# RightPannel.net
KiCad netlist of a schematic drawn in Altium Designer
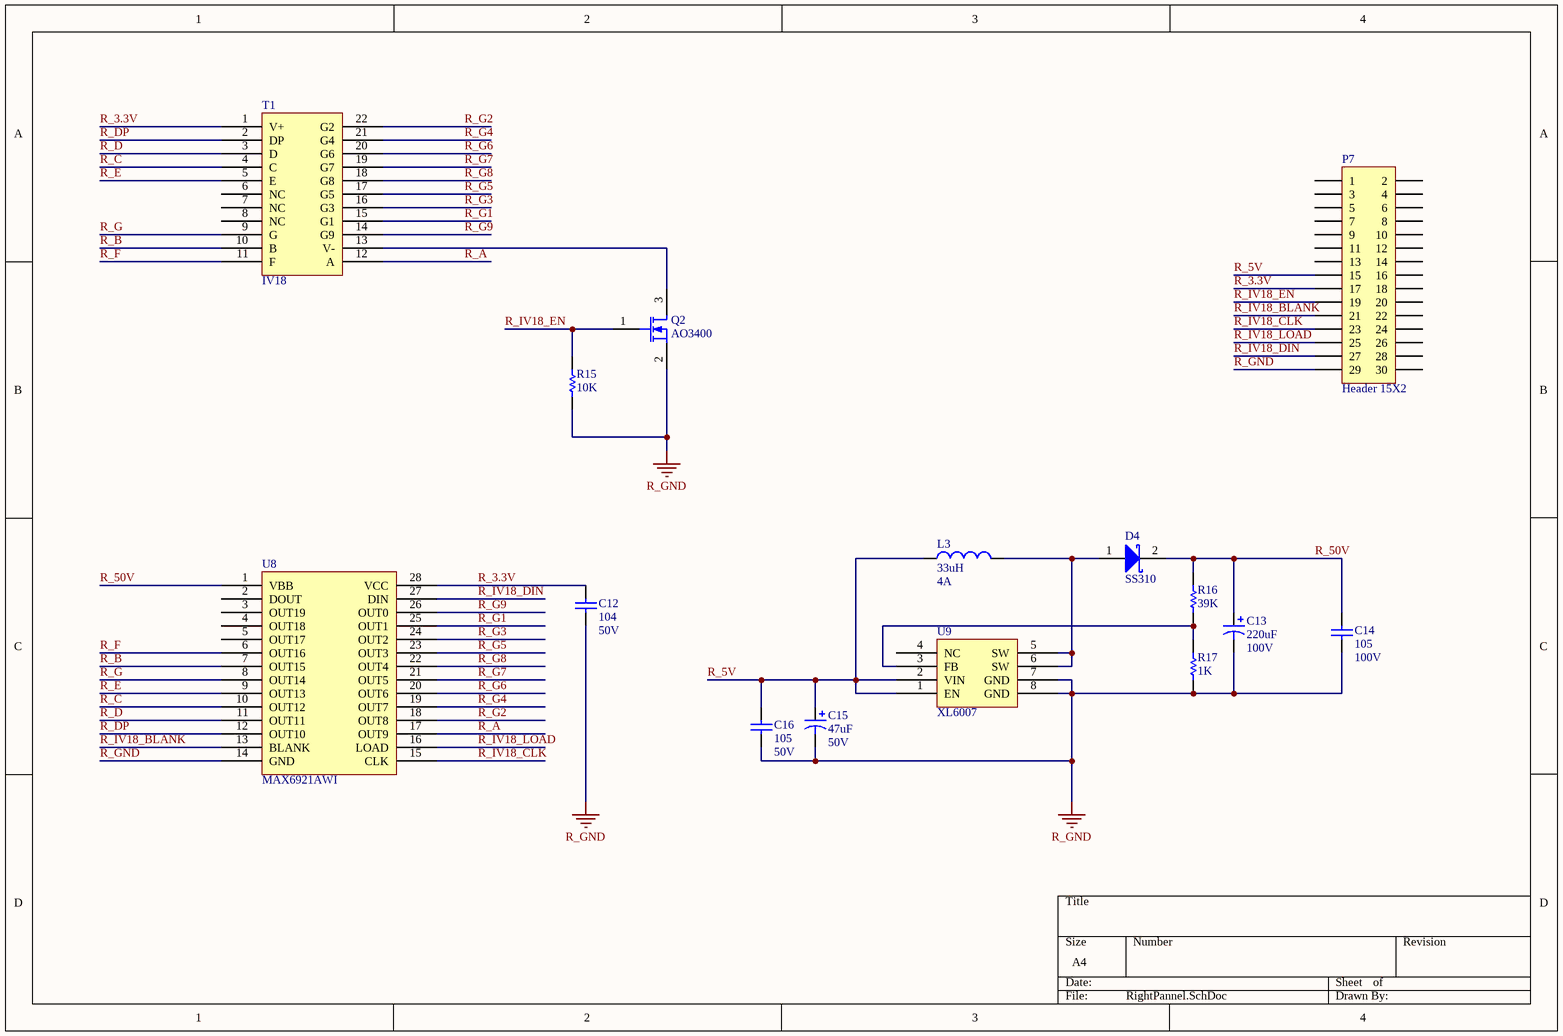
[diagram p0: RightPannel.SchDoc]

(export (version "E")
  (design (tool "Eeschema 10.0.6"))
  (components
    (comp (ref "C12")
      (value "50V")
      (footprint "NeoIVClock:CAPC1608L")
      (description "Capacitor")
      (fields (field (name "ALTIUM_VALUE") "104") (field (name "PUBLISHER") "Altium Limited"))
      (libsource (lib "Miscellaneous Devices") (part "Cap"))
    )
    (comp (ref "C13")
      (value "100V")
      (footprint "NeoIVClock:SMD-EC-F16")
      (description "Polarized Capacitor (Radial)")
      (fields (field (name "ALTIUM_VALUE") "220uF") (field (name "PUBLISHER") "Altium Limited"))
      (libsource (lib "Miscellaneous Devices") (part "Cap Pol1"))
    )
    (comp (ref "C14")
      (value "100V")
      (footprint "NeoIVClock:CAPC2012L")
      (description "Capacitor")
      (fields (field (name "ALTIUM_VALUE") "105") (field (name "PUBLISHER") "Altium Limited"))
      (libsource (lib "Miscellaneous Devices") (part "Cap"))
    )
    (comp (ref "C15")
      (value "50V")
      (footprint "NeoIVClock:SMD-EC-F6.3")
      (description "Polarized Capacitor (Radial)")
      (fields (field (name "ALTIUM_VALUE") "47uF") (field (name "PUBLISHER") "Altium Limited"))
      (libsource (lib "Miscellaneous Devices") (part "Cap Pol1"))
    )
    (comp (ref "C16")
      (value "50V")
      (footprint "NeoIVClock:CAPC1608L")
      (description "Capacitor")
      (fields (field (name "ALTIUM_VALUE") "105") (field (name "PUBLISHER") "Altium Limited"))
      (libsource (lib "Miscellaneous Devices") (part "Cap"))
    )
    (comp (ref "D4")
      (value "SS310")
      (footprint "NeoIVClock:DO-214AC-SMA")
      (description "Schottky Diode")
      (fields (field (name "PUBLISHER") "Altium Limited"))
      (libsource (lib "Miscellaneous Devices") (part "D Schottky"))
    )
    (comp (ref "L3")
      (value "4A")
      (footprint "NeoIVClock:CYH125")
      (description "Inductor")
      (fields (field (name "ALTIUM_VALUE") "33uH") (field (name "PUBLISHER") "Altium Limited"))
      (libsource (lib "Miscellaneous Devices") (part "Inductor"))
    )
    (comp (ref "P7")
      (value "Header 15X2")
      (footprint "HDR2X15")
      (description "Header, 15-Pin, Dual row")
      (fields (field (name "PUBLISHER") "Altium Limited"))
      (libsource (lib "Miscellaneous Connectors") (part "Header 15X2"))
    )
    (comp (ref "Q2")
      (value "AO3400")
      (footprint "NeoIVClock:SOT-23B_L")
      (description "N-Channel MOSFET")
      (fields (field (name "PUBLISHER") "Altium Limited"))
      (libsource (lib "Miscellaneous Devices") (part "MOSFET-N"))
    )
    (comp (ref "R15")
      (value "10K")
      (footprint "NeoIVClock:RESC1608L")
      (description "Resistor")
      (fields (field (name "Comment") "Res1") (field (name "PUBLISHER") "Altium Limited"))
      (libsource (lib "Miscellaneous Devices") (part "Res1"))
    )
    (comp (ref "R16")
      (value "39K")
      (footprint "NeoIVClock:RESC1608L")
      (description "Resistor")
      (fields (field (name "Comment") "Res1") (field (name "PUBLISHER") "Altium Limited"))
      (libsource (lib "Miscellaneous Devices") (part "Res1"))
    )
    (comp (ref "R17")
      (value "1K")
      (footprint "NeoIVClock:RESC1608L")
      (description "Resistor")
      (fields (field (name "Comment") "Res1") (field (name "PUBLISHER") "Altium Limited"))
      (libsource (lib "Miscellaneous Devices") (part "Res1"))
    )
    (comp (ref "T1")
      (value "IV18")
      (footprint "NeoIVClock:IV18")
      (libsource (lib "NeoIVClock") (part "IV18"))
    )
    (comp (ref "U8")
      (value "MAX6921AWI")
      (footprint "NeoIVClock:SOIC127P1032X265-28N")
      (libsource (lib "NeoIVClock") (part "MAX6921AWI"))
    )
    (comp (ref "U9")
      (value "XL6007")
      (footprint "NeoIVClock:SOP127P780-8L")
      (libsource (lib "NeoIVClock") (part "XL6007"))
    )
  )
  (nets
    (net (code "1") (name "/R_3.3V") (class "Default")
      (node (ref "C12") (pin "2") (pinfunction "2_2") (pintype "passive"))
      (node (ref "P7") (pin "17") (pinfunction "17_17") (pintype "passive"))
      (node (ref "T1") (pin "1") (pinfunction "V+_1") (pintype "passive"))
      (node (ref "U8") (pin "28") (pinfunction "VCC_28") (pintype "passive"))
    )
    (net (code "2") (name "/R_5V") (class "Default")
      (node (ref "C15") (pin "1") (pinfunction "1_1") (pintype "passive"))
      (node (ref "C16") (pin "2") (pinfunction "2_2") (pintype "passive"))
      (node (ref "L3") (pin "1") (pinfunction "1_1") (pintype "passive"))
      (node (ref "P7") (pin "15") (pinfunction "15_15") (pintype "passive"))
      (node (ref "U9") (pin "1") (pinfunction "EN_1") (pintype "passive"))
      (node (ref "U9") (pin "2") (pinfunction "VIN_2") (pintype "passive"))
    )
    (net (code "3") (name "/R_50V") (class "Default")
      (node (ref "C13") (pin "1") (pinfunction "1_1") (pintype "passive"))
      (node (ref "C14") (pin "2") (pinfunction "2_2") (pintype "passive"))
      (node (ref "D4") (pin "2") (pinfunction "K_2") (pintype "passive"))
      (node (ref "R16") (pin "1") (pinfunction "1_1") (pintype "passive"))
      (node (ref "U8") (pin "1") (pinfunction "VBB_1") (pintype "passive"))
    )
    (net (code "4") (name "/R_A") (class "Default")
      (node (ref "T1") (pin "12") (pinfunction "A_12") (pintype "passive"))
      (node (ref "U8") (pin "17") (pinfunction "OUT9_17") (pintype "passive"))
    )
    (net (code "5") (name "/R_B") (class "Default")
      (node (ref "T1") (pin "10") (pinfunction "B_10") (pintype "passive"))
      (node (ref "U8") (pin "7") (pinfunction "OUT15_7") (pintype "passive"))
    )
    (net (code "6") (name "/R_C") (class "Default")
      (node (ref "T1") (pin "4") (pinfunction "C_4") (pintype "passive"))
      (node (ref "U8") (pin "10") (pinfunction "OUT12_10") (pintype "passive"))
    )
    (net (code "7") (name "/R_D") (class "Default")
      (node (ref "T1") (pin "3") (pinfunction "D_3") (pintype "passive"))
      (node (ref "U8") (pin "11") (pinfunction "OUT11_11") (pintype "passive"))
    )
    (net (code "8") (name "/R_DP") (class "Default")
      (node (ref "T1") (pin "2") (pinfunction "DP_2") (pintype "passive"))
      (node (ref "U8") (pin "12") (pinfunction "OUT10_12") (pintype "passive"))
    )
    (net (code "9") (name "/R_E") (class "Default")
      (node (ref "T1") (pin "5") (pinfunction "E_5") (pintype "passive"))
      (node (ref "U8") (pin "9") (pinfunction "OUT13_9") (pintype "passive"))
    )
    (net (code "10") (name "/R_F") (class "Default")
      (node (ref "T1") (pin "11") (pinfunction "F_11") (pintype "passive"))
      (node (ref "U8") (pin "6") (pinfunction "OUT16_6") (pintype "passive"))
    )
    (net (code "11") (name "/R_G") (class "Default")
      (node (ref "T1") (pin "9") (pinfunction "G_9") (pintype "passive"))
      (node (ref "U8") (pin "8") (pinfunction "OUT14_8") (pintype "passive"))
    )
    (net (code "12") (name "/R_G1") (class "Default")
      (node (ref "T1") (pin "15") (pinfunction "G1_15") (pintype "passive"))
      (node (ref "U8") (pin "25") (pinfunction "OUT1_25") (pintype "passive"))
    )
    (net (code "13") (name "/R_G2") (class "Default")
      (node (ref "T1") (pin "22") (pinfunction "G2_22") (pintype "passive"))
      (node (ref "U8") (pin "18") (pinfunction "OUT8_18") (pintype "passive"))
    )
    (net (code "14") (name "/R_G3") (class "Default")
      (node (ref "T1") (pin "16") (pinfunction "G3_16") (pintype "passive"))
      (node (ref "U8") (pin "24") (pinfunction "OUT2_24") (pintype "passive"))
    )
    (net (code "15") (name "/R_G4") (class "Default")
      (node (ref "T1") (pin "21") (pinfunction "G4_21") (pintype "passive"))
      (node (ref "U8") (pin "19") (pinfunction "OUT7_19") (pintype "passive"))
    )
    (net (code "16") (name "/R_G5") (class "Default")
      (node (ref "T1") (pin "17") (pinfunction "G5_17") (pintype "passive"))
      (node (ref "U8") (pin "23") (pinfunction "OUT3_23") (pintype "passive"))
    )
    (net (code "17") (name "/R_G6") (class "Default")
      (node (ref "T1") (pin "20") (pinfunction "G6_20") (pintype "passive"))
      (node (ref "U8") (pin "20") (pinfunction "OUT6_20") (pintype "passive"))
    )
    (net (code "18") (name "/R_G7") (class "Default")
      (node (ref "T1") (pin "19") (pinfunction "G7_19") (pintype "passive"))
      (node (ref "U8") (pin "21") (pinfunction "OUT5_21") (pintype "passive"))
    )
    (net (code "19") (name "/R_G8") (class "Default")
      (node (ref "T1") (pin "18") (pinfunction "G8_18") (pintype "passive"))
      (node (ref "U8") (pin "22") (pinfunction "OUT4_22") (pintype "passive"))
    )
    (net (code "20") (name "/R_G9") (class "Default")
      (node (ref "T1") (pin "14") (pinfunction "G9_14") (pintype "passive"))
      (node (ref "U8") (pin "26") (pinfunction "OUT0_26") (pintype "passive"))
    )
    (net (code "21") (name "/R_IV18_BLANK") (class "Default")
      (node (ref "P7") (pin "21") (pinfunction "21_21") (pintype "passive"))
      (node (ref "U8") (pin "13") (pinfunction "BLANK_13") (pintype "passive"))
    )
    (net (code "22") (name "/R_IV18_CLK") (class "Default")
      (node (ref "P7") (pin "23") (pinfunction "23_23") (pintype "passive"))
      (node (ref "U8") (pin "15") (pinfunction "CLK_15") (pintype "passive"))
    )
    (net (code "23") (name "/R_IV18_DIN") (class "Default")
      (node (ref "P7") (pin "27") (pinfunction "27_27") (pintype "passive"))
      (node (ref "U8") (pin "27") (pinfunction "DIN_27") (pintype "passive"))
    )
    (net (code "24") (name "/R_IV18_EN") (class "Default")
      (node (ref "P7") (pin "19") (pinfunction "19_19") (pintype "passive"))
      (node (ref "Q2") (pin "1") (pinfunction "G_1") (pintype "passive"))
      (node (ref "R15") (pin "1") (pinfunction "1_1") (pintype "passive"))
    )
    (net (code "25") (name "/R_IV18_LOAD") (class "Default")
      (node (ref "P7") (pin "25") (pinfunction "25_25") (pintype "passive"))
      (node (ref "U8") (pin "16") (pinfunction "LOAD_16") (pintype "passive"))
    )
    (net (code "26") (name "Net-(D4-A)") (class "Default")
      (node (ref "D4") (pin "1") (pinfunction "A_1") (pintype "passive"))
      (node (ref "L3") (pin "2") (pinfunction "2_2") (pintype "passive"))
      (node (ref "U9") (pin "5") (pinfunction "SW_5") (pintype "passive"))
      (node (ref "U9") (pin "6") (pinfunction "SW_6") (pintype "passive"))
    )
    (net (code "27") (name "Net-(Q2-D)") (class "Default")
      (node (ref "Q2") (pin "3") (pinfunction "D_3") (pintype "passive"))
      (node (ref "T1") (pin "13") (pinfunction "V-_13") (pintype "passive"))
    )
    (net (code "28") (name "Net-(U9-FB)") (class "Default")
      (node (ref "R16") (pin "2") (pinfunction "2_2") (pintype "passive"))
      (node (ref "R17") (pin "1") (pinfunction "1_1") (pintype "passive"))
      (node (ref "U9") (pin "3") (pinfunction "FB_3") (pintype "passive"))
    )
    (net (code "29") (name "R_GND") (class "Default")
      (node (ref "C12") (pin "1") (pinfunction "1_1") (pintype "passive"))
      (node (ref "C13") (pin "2") (pinfunction "2_2") (pintype "passive"))
      (node (ref "C14") (pin "1") (pinfunction "1_1") (pintype "passive"))
      (node (ref "C15") (pin "2") (pinfunction "2_2") (pintype "passive"))
      (node (ref "C16") (pin "1") (pinfunction "1_1") (pintype "passive"))
      (node (ref "P7") (pin "29") (pinfunction "29_29") (pintype "passive"))
      (node (ref "Q2") (pin "2") (pinfunction "S_2") (pintype "passive"))
      (node (ref "R15") (pin "2") (pinfunction "2_2") (pintype "passive"))
      (node (ref "R17") (pin "2") (pinfunction "2_2") (pintype "passive"))
      (node (ref "U8") (pin "14") (pinfunction "GND_14") (pintype "passive"))
      (node (ref "U9") (pin "7") (pinfunction "GND_7") (pintype "passive"))
      (node (ref "U9") (pin "8") (pinfunction "GND_8") (pintype "passive"))
    )
    (net (code "30") (name "unconnected-(P7-Pad1)") (class "Default")
      (node (ref "P7") (pin "1") (pinfunction "1_1") (pintype "passive"))
    )
    (net (code "31") (name "unconnected-(P7-Pad2)") (class "Default")
      (node (ref "P7") (pin "2") (pinfunction "2_2") (pintype "passive"))
    )
    (net (code "32") (name "unconnected-(P7-Pad3)") (class "Default")
      (node (ref "P7") (pin "3") (pinfunction "3_3") (pintype "passive"))
    )
    (net (code "33") (name "unconnected-(P7-Pad4)") (class "Default")
      (node (ref "P7") (pin "4") (pinfunction "4_4") (pintype "passive"))
    )
    (net (code "34") (name "unconnected-(P7-Pad5)") (class "Default")
      (node (ref "P7") (pin "5") (pinfunction "5_5") (pintype "passive"))
    )
    (net (code "35") (name "unconnected-(P7-Pad6)") (class "Default")
      (node (ref "P7") (pin "6") (pinfunction "6_6") (pintype "passive"))
    )
    (net (code "36") (name "unconnected-(P7-Pad7)") (class "Default")
      (node (ref "P7") (pin "7") (pinfunction "7_7") (pintype "passive"))
    )
    (net (code "37") (name "unconnected-(P7-Pad8)") (class "Default")
      (node (ref "P7") (pin "8") (pinfunction "8_8") (pintype "passive"))
    )
    (net (code "38") (name "unconnected-(P7-Pad9)") (class "Default")
      (node (ref "P7") (pin "9") (pinfunction "9_9") (pintype "passive"))
    )
    (net (code "39") (name "unconnected-(P7-Pad10)") (class "Default")
      (node (ref "P7") (pin "10") (pinfunction "10_10") (pintype "passive"))
    )
    (net (code "40") (name "unconnected-(P7-Pad11)") (class "Default")
      (node (ref "P7") (pin "11") (pinfunction "11_11") (pintype "passive"))
    )
    (net (code "41") (name "unconnected-(P7-Pad12)") (class "Default")
      (node (ref "P7") (pin "12") (pinfunction "12_12") (pintype "passive"))
    )
    (net (code "42") (name "unconnected-(P7-Pad13)") (class "Default")
      (node (ref "P7") (pin "13") (pinfunction "13_13") (pintype "passive"))
    )
    (net (code "43") (name "unconnected-(P7-Pad14)") (class "Default")
      (node (ref "P7") (pin "14") (pinfunction "14_14") (pintype "passive"))
    )
    (net (code "44") (name "unconnected-(P7-Pad16)") (class "Default")
      (node (ref "P7") (pin "16") (pinfunction "16_16") (pintype "passive"))
    )
    (net (code "45") (name "unconnected-(P7-Pad18)") (class "Default")
      (node (ref "P7") (pin "18") (pinfunction "18_18") (pintype "passive"))
    )
    (net (code "46") (name "unconnected-(P7-Pad20)") (class "Default")
      (node (ref "P7") (pin "20") (pinfunction "20_20") (pintype "passive"))
    )
    (net (code "47") (name "unconnected-(P7-Pad22)") (class "Default")
      (node (ref "P7") (pin "22") (pinfunction "22_22") (pintype "passive"))
    )
    (net (code "48") (name "unconnected-(P7-Pad24)") (class "Default")
      (node (ref "P7") (pin "24") (pinfunction "24_24") (pintype "passive"))
    )
    (net (code "49") (name "unconnected-(P7-Pad26)") (class "Default")
      (node (ref "P7") (pin "26") (pinfunction "26_26") (pintype "passive"))
    )
    (net (code "50") (name "unconnected-(P7-Pad28)") (class "Default")
      (node (ref "P7") (pin "28") (pinfunction "28_28") (pintype "passive"))
    )
    (net (code "51") (name "unconnected-(P7-Pad30)") (class "Default")
      (node (ref "P7") (pin "30") (pinfunction "30_30") (pintype "passive"))
    )
    (net (code "52") (name "unconnected-(T1-NC-Pad6)") (class "Default")
      (node (ref "T1") (pin "6") (pinfunction "NC_6") (pintype "passive"))
    )
    (net (code "53") (name "unconnected-(T1-NC-Pad7)") (class "Default")
      (node (ref "T1") (pin "7") (pinfunction "NC_7") (pintype "passive"))
    )
    (net (code "54") (name "unconnected-(T1-NC-Pad8)") (class "Default")
      (node (ref "T1") (pin "8") (pinfunction "NC_8") (pintype "passive"))
    )
    (net (code "55") (name "unconnected-(U8-DOUT-Pad2)") (class "Default")
      (node (ref "U8") (pin "2") (pinfunction "DOUT_2") (pintype "passive"))
    )
    (net (code "56") (name "unconnected-(U8-OUT17-Pad5)") (class "Default")
      (node (ref "U8") (pin "5") (pinfunction "OUT17_5") (pintype "passive"))
    )
    (net (code "57") (name "unconnected-(U8-OUT18-Pad4)") (class "Default")
      (node (ref "U8") (pin "4") (pinfunction "OUT18_4") (pintype "passive"))
    )
    (net (code "58") (name "unconnected-(U8-OUT19-Pad3)") (class "Default")
      (node (ref "U8") (pin "3") (pinfunction "OUT19_3") (pintype "passive"))
    )
    (net (code "59") (name "unconnected-(U9-NC-Pad4)") (class "Default")
      (node (ref "U9") (pin "4") (pinfunction "NC_4") (pintype "passive"))
    )
  )
)
